# BinaryClock_Control.net
KiCad netlist of a schematic drawn in Altium Designer
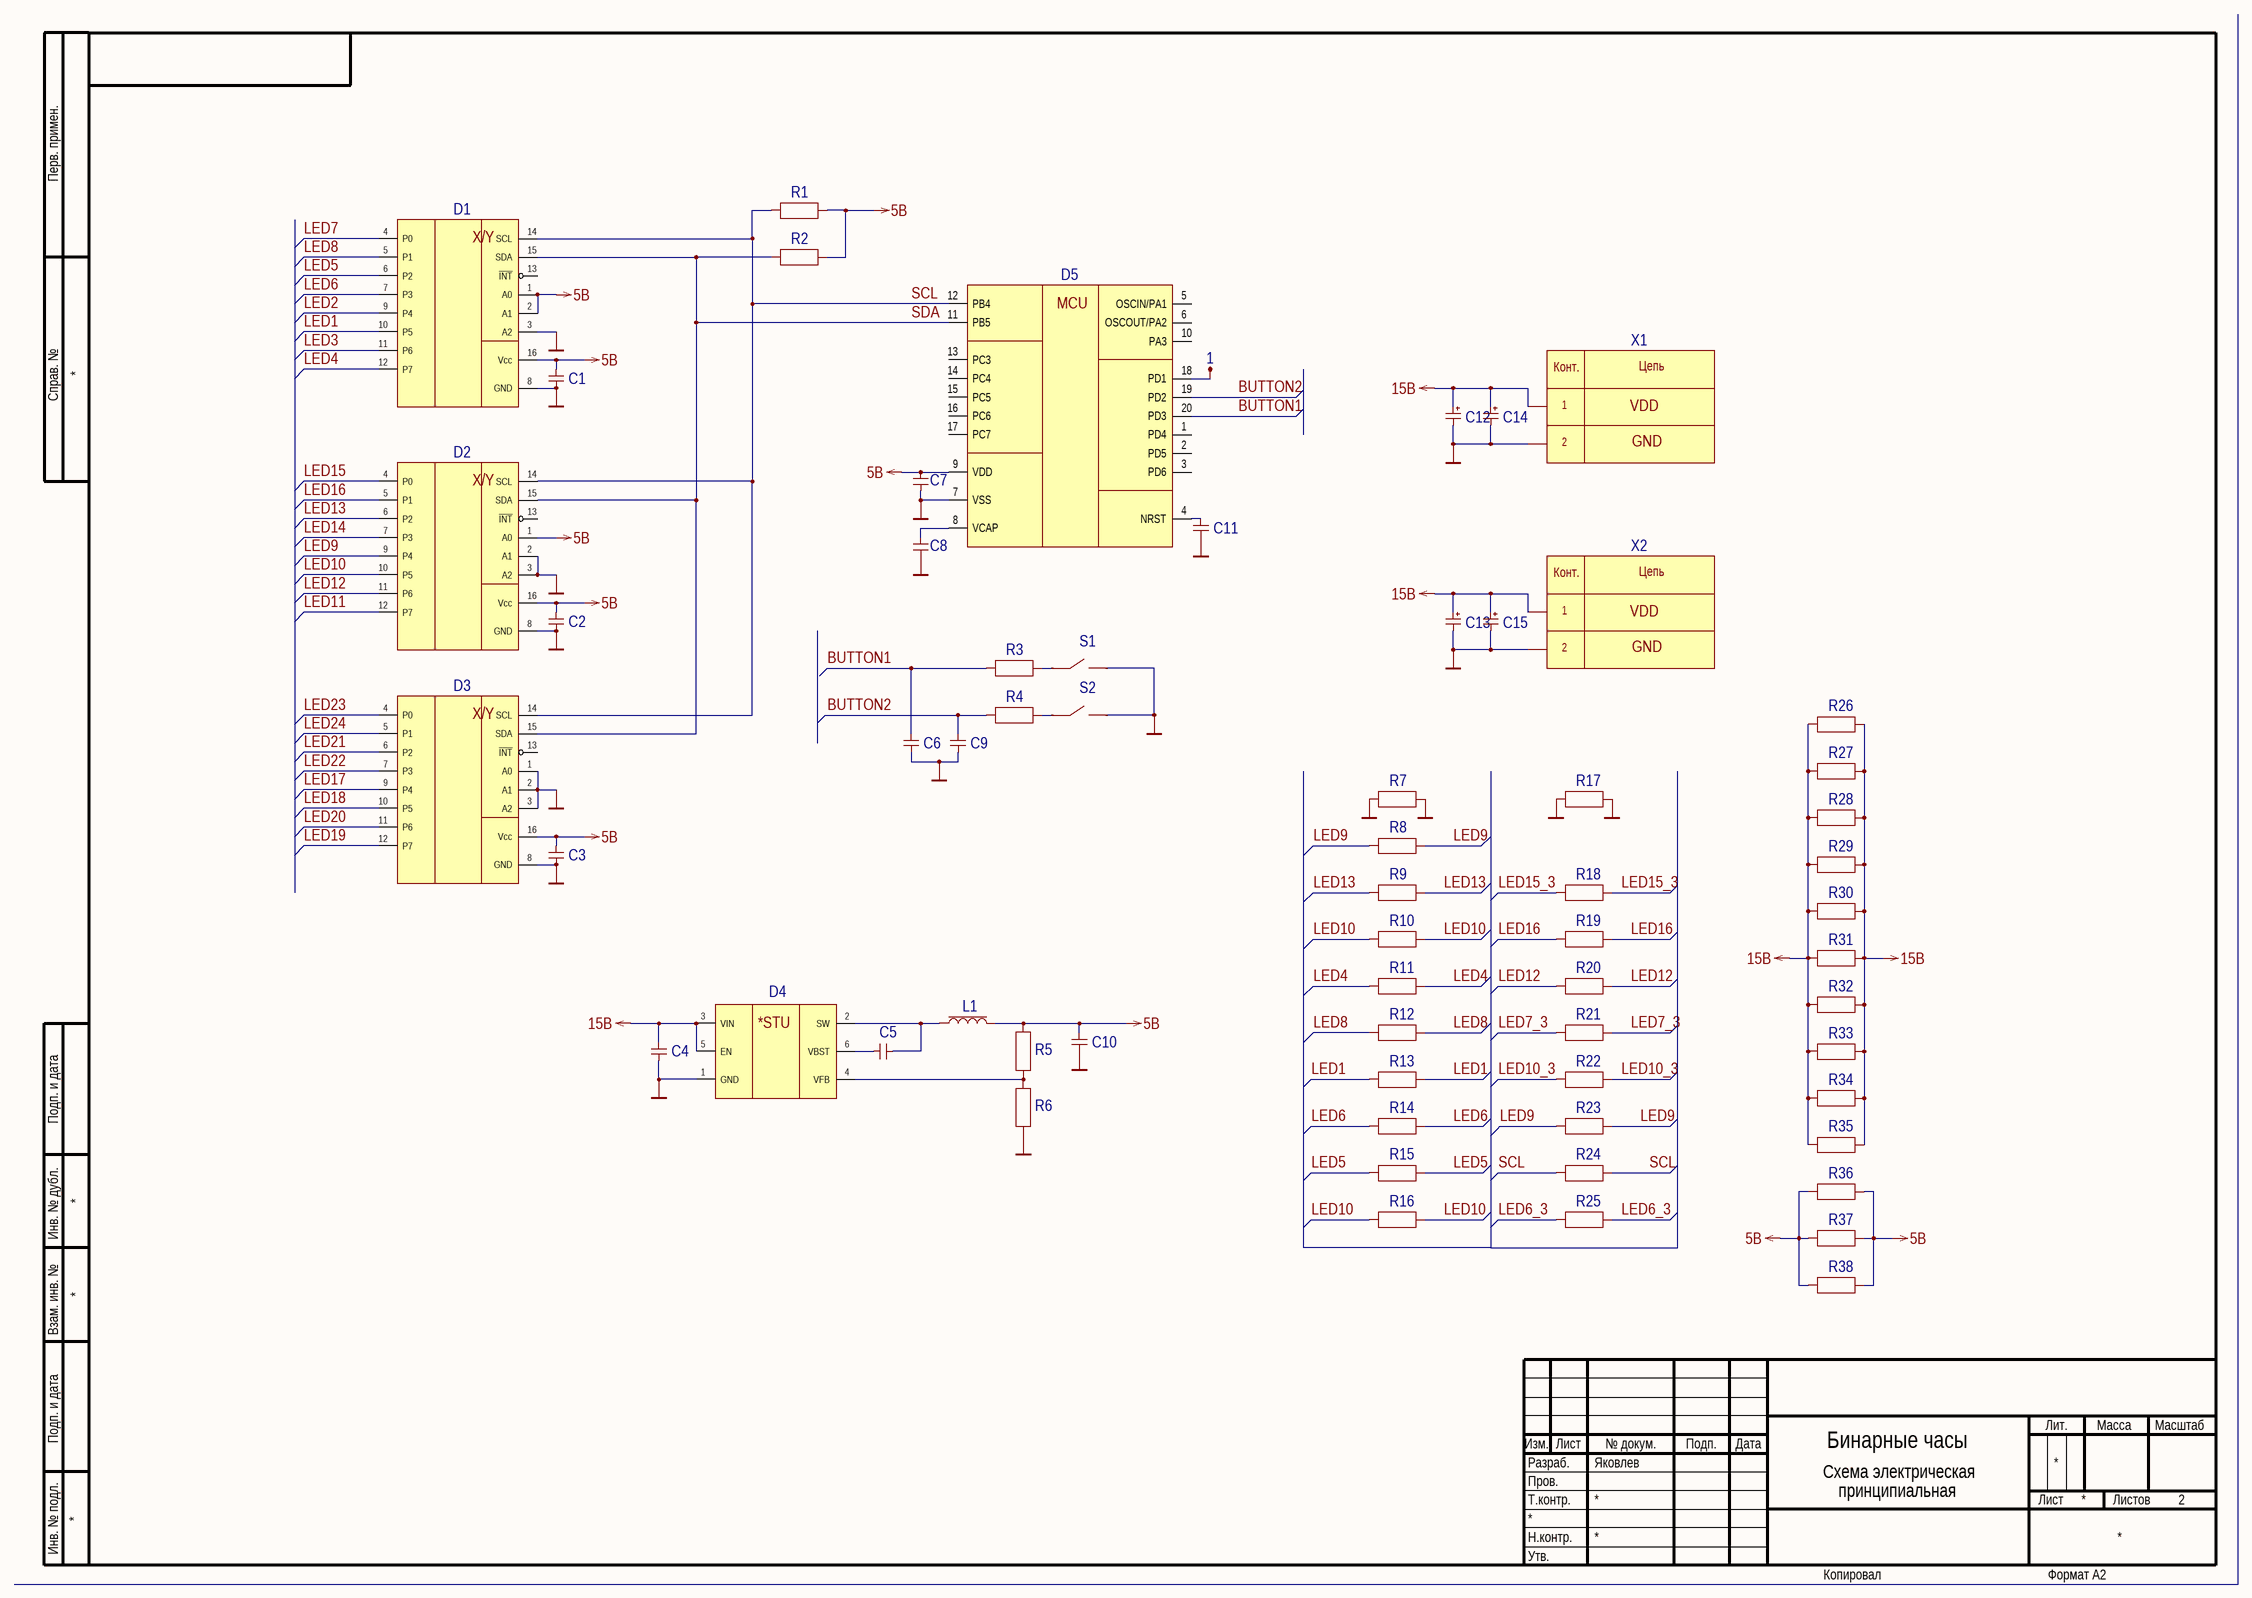
[diagram p0: BinaryClock_Control.SchDoc]

(export (version "E")
  (design (tool "Eeschema 10.0.6"))
  (components
    (comp (ref "1") (value "Point") (footprint "point") (libsource (lib "Passive,Diodes") (part "Point")))
    (comp (ref "C1")
      (value "0805-16 В-X7R-0,1мкФ±10 %")
      (footprint "SMD-0805C")
      (description "Capacitor")
      (fields (field (name "MANUFACTURER") "Murata"))
      (libsource (lib "Passive,Diodes") (part "Cap"))
    )
    (comp (ref "C2")
      (value "0805-16 В-X7R-0,1мкФ±10 %")
      (footprint "SMD-0805C")
      (description "Capacitor")
      (fields (field (name "MANUFACTURER") "Murata"))
      (libsource (lib "Passive,Diodes") (part "Cap"))
    )
    (comp (ref "C3")
      (value "0805-16 В-X7R-0,1мкФ±10 %")
      (footprint "SMD-0805C")
      (description "Capacitor")
      (fields (field (name "MANUFACTURER") "Murata"))
      (libsource (lib "Passive,Diodes") (part "Cap"))
    )
    (comp (ref "C4")
      (value "1206-16 В-X7R-22мкФ±10 %")
      (footprint "SMD-1206C")
      (description "Capacitor")
      (libsource (lib "Passive,Diodes") (part "Cap"))
    )
    (comp (ref "C5")
      (value "0805-16 В-X7R-0,1мкФ±10 %")
      (footprint "SMD-0805C")
      (description "Capacitor")
      (fields (field (name "MANUFACTURER") "Murata"))
      (libsource (lib "Passive,Diodes") (part "Cap"))
    )
    (comp (ref "C6")
      (value "0805-16 В-X7R-0,1мкФ±10 %")
      (footprint "SMD-0805C")
      (description "Capacitor")
      (fields (field (name "MANUFACTURER") "Murata"))
      (libsource (lib "Passive,Diodes") (part "Cap"))
    )
    (comp (ref "C7")
      (value "0805-16 В-X7R-0,1мкФ±10 %")
      (footprint "SMD-0805C")
      (description "Capacitor")
      (fields (field (name "MANUFACTURER") "Murata"))
      (libsource (lib "Passive,Diodes") (part "Cap"))
    )
    (comp (ref "C8")
      (value "0805-16 В-X7R-1мкФ±10 %")
      (footprint "SMD-0805C")
      (description "Capacitor")
      (fields (field (name "MANUFACTURER") "Murata"))
      (libsource (lib "Passive,Diodes") (part "Cap"))
    )
    (comp (ref "C9")
      (value "0805-16 В-X7R-0,1мкФ±10 %")
      (footprint "SMD-0805C")
      (description "Capacitor")
      (fields (field (name "MANUFACTURER") "Murata"))
      (libsource (lib "Passive,Diodes") (part "Cap"))
    )
    (comp (ref "C10")
      (value "1206-16 В-X7R-22мкФ±10 %")
      (footprint "SMD-1206C")
      (description "Capacitor")
      (libsource (lib "Passive,Diodes") (part "Cap"))
    )
    (comp (ref "C11")
      (value "0805-16 В-X7R-0,1мкФ±10 %")
      (footprint "SMD-0805C")
      (description "Capacitor")
      (fields (field (name "MANUFACTURER") "Murata"))
      (libsource (lib "Passive,Diodes") (part "Cap"))
    )
    (comp (ref "C12")
      (value "D-20 В-47 мкФ±10 %")
      (footprint "CAP POL 2917/7343")
      (description "Electrolytic capacitor")
      (libsource (lib "Passive,Diodes") (part "Cap_el"))
    )
    (comp (ref "C13")
      (value "D-20 В-47 мкФ±10 %")
      (footprint "CAP POL 2917/7343")
      (description "Electrolytic capacitor")
      (libsource (lib "Passive,Diodes") (part "Cap_el"))
    )
    (comp (ref "C14")
      (value "D-20 В-47 мкФ±10 %")
      (footprint "CAP POL 2917/7343")
      (description "Electrolytic capacitor")
      (libsource (lib "Passive,Diodes") (part "Cap_el"))
    )
    (comp (ref "C15")
      (value "D-20 В-47 мкФ±10 %")
      (footprint "CAP POL 2917/7343")
      (description "Electrolytic capacitor")
      (libsource (lib "Passive,Diodes") (part "Cap_el"))
    )
    (comp (ref "D1")
      (value "PCF8574T/3.512")
      (footprint "SO-16")
      (description "Remote 8-bit I/O expander for I2C bus")
      (fields (field (name "MANUFACTURER") "NXP"))
      (libsource (lib "Devices") (part "PCF8574"))
    )
    (comp (ref "D2")
      (value "PCF8574T/3.512")
      (footprint "SO-16")
      (description "Remote 8-bit I/O expander for I2C bus")
      (fields (field (name "MANUFACTURER") "NXP"))
      (libsource (lib "Devices") (part "PCF8574"))
    )
    (comp (ref "D3")
      (value "PCF8574T/3.512")
      (footprint "SO-16")
      (description "Remote 8-bit I/O expander for I2C bus")
      (fields (field (name "MANUFACTURER") "NXP"))
      (libsource (lib "Devices") (part "PCF8574"))
    )
    (comp (ref "D4")
      (value "TPS562200DDCT")
      (footprint "SOT23-6_M")
      (description "4.5-V To 17-V Input, 2-A, 3-A Synchronous Step-Down Voltage Regulator")
      (fields (field (name "MANUFACTURER") "Texas Instruments"))
      (libsource (lib "Devices") (part "TPS562200"))
    )
    (comp (ref "D5")
      (value "STM8S103F3P6")
      (footprint "TSSOP-20")
      (fields (field (name "MANUFACTURER") "STMicroelectronics"))
      (libsource (lib "Devices") (part "STM8S103FxP"))
    )
    (comp (ref "L1")
      (value "NLCV32T-4R7M-EF")
      (footprint "1210_M")
      (description "Inductor")
      (fields (field (name "MANUFACTURER") "TDK"))
      (libsource (lib "Passive,Diodes") (part "Inductor"))
    )
    (comp (ref "R1")
      (value "0805±5 %-10 кОм")
      (footprint "SMD-0805-RES")
      (description "Resistor")
      (libsource (lib "Passive,Diodes") (part "Res"))
    )
    (comp (ref "R2")
      (value "0805±5 %-10 кОм")
      (footprint "SMD-0805-RES")
      (description "Resistor")
      (libsource (lib "Passive,Diodes") (part "Res"))
    )
    (comp (ref "R3")
      (value "0805±5 %-100 Ом")
      (footprint "SMD-0805-RES")
      (description "Resistor")
      (libsource (lib "Passive,Diodes") (part "Res"))
    )
    (comp (ref "R4")
      (value "0805±5 %-100 Ом")
      (footprint "SMD-0805-RES")
      (description "Resistor")
      (libsource (lib "Passive,Diodes") (part "Res"))
    )
    (comp (ref "R5")
      (value "0805±1 %-56,2 кОм")
      (footprint "SMD-0805-RES")
      (description "Resistor")
      (libsource (lib "Passive,Diodes") (part "Res"))
    )
    (comp (ref "R6")
      (value "0805±1 %-10,2 кОм")
      (footprint "SMD-0805-RES")
      (description "Resistor")
      (libsource (lib "Passive,Diodes") (part "Res"))
    )
    (comp (ref "R7")
      (value "0805±5 %-0 Ом")
      (footprint "R1206")
      (description "Resistor")
      (libsource (lib "Passive,Diodes") (part "Res"))
    )
    (comp (ref "R8")
      (value "0805±5 %-0 Ом")
      (footprint "R1206")
      (description "Resistor")
      (libsource (lib "Passive,Diodes") (part "Res"))
    )
    (comp (ref "R9")
      (value "0805±5 %-0 Ом")
      (footprint "R1206")
      (description "Resistor")
      (libsource (lib "Passive,Diodes") (part "Res"))
    )
    (comp (ref "R10")
      (value "0805±5 %-0 Ом")
      (footprint "R1206")
      (description "Resistor")
      (libsource (lib "Passive,Diodes") (part "Res"))
    )
    (comp (ref "R11")
      (value "0805±5 %-0 Ом")
      (footprint "R1206")
      (description "Resistor")
      (libsource (lib "Passive,Diodes") (part "Res"))
    )
    (comp (ref "R12")
      (value "0805±5 %-0 Ом")
      (footprint "R1206")
      (description "Resistor")
      (libsource (lib "Passive,Diodes") (part "Res"))
    )
    (comp (ref "R13")
      (value "0805±5 %-0 Ом")
      (footprint "R1206")
      (description "Resistor")
      (libsource (lib "Passive,Diodes") (part "Res"))
    )
    (comp (ref "R14")
      (value "0805±5 %-0 Ом")
      (footprint "R1206")
      (description "Resistor")
      (libsource (lib "Passive,Diodes") (part "Res"))
    )
    (comp (ref "R15")
      (value "0805±5 %-0 Ом")
      (footprint "R1206")
      (description "Resistor")
      (libsource (lib "Passive,Diodes") (part "Res"))
    )
    (comp (ref "R16")
      (value "0805±5 %-0 Ом")
      (footprint "R1206")
      (description "Resistor")
      (libsource (lib "Passive,Diodes") (part "Res"))
    )
    (comp (ref "R17")
      (value "0805±5 %-0 Ом")
      (footprint "R1206")
      (description "Resistor")
      (libsource (lib "Passive,Diodes") (part "Res"))
    )
    (comp (ref "R18")
      (value "0805±5 %-0 Ом")
      (footprint "R1206")
      (description "Resistor")
      (libsource (lib "Passive,Diodes") (part "Res"))
    )
    (comp (ref "R19")
      (value "0805±5 %-0 Ом")
      (footprint "R1206")
      (description "Resistor")
      (libsource (lib "Passive,Diodes") (part "Res"))
    )
    (comp (ref "R20")
      (value "0805±5 %-0 Ом")
      (footprint "R1206")
      (description "Resistor")
      (libsource (lib "Passive,Diodes") (part "Res"))
    )
    (comp (ref "R21")
      (value "0805±5 %-0 Ом")
      (footprint "R1206")
      (description "Resistor")
      (libsource (lib "Passive,Diodes") (part "Res"))
    )
    (comp (ref "R22")
      (value "0805±5 %-0 Ом")
      (footprint "R1206")
      (description "Resistor")
      (libsource (lib "Passive,Diodes") (part "Res"))
    )
    (comp (ref "R23")
      (value "0805±5 %-0 Ом")
      (footprint "R1206")
      (description "Resistor")
      (libsource (lib "Passive,Diodes") (part "Res"))
    )
    (comp (ref "R24")
      (value "0805±5 %-0 Ом")
      (footprint "R1206")
      (description "Resistor")
      (libsource (lib "Passive,Diodes") (part "Res"))
    )
    (comp (ref "R25")
      (value "0805±5 %-0 Ом")
      (footprint "R1206")
      (description "Resistor")
      (libsource (lib "Passive,Diodes") (part "Res"))
    )
    (comp (ref "R26")
      (value "0805±5 %-0 Ом")
      (footprint "R1206")
      (description "Resistor")
      (libsource (lib "Passive,Diodes") (part "Res"))
    )
    (comp (ref "R27")
      (value "0805±5 %-0 Ом")
      (footprint "R1206")
      (description "Resistor")
      (libsource (lib "Passive,Diodes") (part "Res"))
    )
    (comp (ref "R28")
      (value "0805±5 %-0 Ом")
      (footprint "R1206")
      (description "Resistor")
      (libsource (lib "Passive,Diodes") (part "Res"))
    )
    (comp (ref "R29")
      (value "0805±5 %-0 Ом")
      (footprint "R1206")
      (description "Resistor")
      (libsource (lib "Passive,Diodes") (part "Res"))
    )
    (comp (ref "R30")
      (value "0805±5 %-0 Ом")
      (footprint "R1206")
      (description "Resistor")
      (libsource (lib "Passive,Diodes") (part "Res"))
    )
    (comp (ref "R31")
      (value "0805±5 %-0 Ом")
      (footprint "R1206")
      (description "Resistor")
      (libsource (lib "Passive,Diodes") (part "Res"))
    )
    (comp (ref "R32")
      (value "0805±5 %-0 Ом")
      (footprint "R1206")
      (description "Resistor")
      (libsource (lib "Passive,Diodes") (part "Res"))
    )
    (comp (ref "R33")
      (value "0805±5 %-0 Ом")
      (footprint "R1206")
      (description "Resistor")
      (libsource (lib "Passive,Diodes") (part "Res"))
    )
    (comp (ref "R34")
      (value "0805±5 %-0 Ом")
      (footprint "R1206")
      (description "Resistor")
      (libsource (lib "Passive,Diodes") (part "Res"))
    )
    (comp (ref "R35")
      (value "0805±5 %-0 Ом")
      (footprint "R1206")
      (description "Resistor")
      (libsource (lib "Passive,Diodes") (part "Res"))
    )
    (comp (ref "R36")
      (value "0805±5 %-0 Ом")
      (footprint "R1206")
      (description "Resistor")
      (libsource (lib "Passive,Diodes") (part "Res"))
    )
    (comp (ref "R37")
      (value "0805±5 %-0 Ом")
      (footprint "R1206")
      (description "Resistor")
      (libsource (lib "Passive,Diodes") (part "Res"))
    )
    (comp (ref "R38")
      (value "0805±5 %-0 Ом")
      (footprint "R1206")
      (description "Resistor")
      (libsource (lib "Passive,Diodes") (part "Res"))
    )
    (comp (ref "S1")
      (value "1243SHIM-160G-G")
      (footprint "1243S")
      (description "Tact button SPST")
      (fields (field (name "MANUFACTURER") "Switronic"))
      (libsource (lib "Connectors") (part "button"))
    )
    (comp (ref "S2")
      (value "1243SHIM-160G-G")
      (footprint "1243S")
      (description "Tact button SPST")
      (fields (field (name "MANUFACTURER") "Switronic"))
      (libsource (lib "Connectors") (part "button"))
    )
    (comp (ref "X1")
      (value "RASM712X")
      (footprint "RASM712")
      (description "Power jack 2.5 mm SMD connector")
      (fields (field (name "MANUFACTURER") "Switchcraft"))
      (libsource (lib "Connectors") (part "RASM712X"))
    )
    (comp (ref "X2")
      (value "RASM712X")
      (footprint "RASM712")
      (description "Power jack 2.5 mm SMD connector")
      (fields (field (name "MANUFACTURER") "Switchcraft"))
      (libsource (lib "Connectors") (part "RASM712X"))
    )
  )
  (nets
    (net (code "1") (name "/BUTTON1") (class "Default")
      (node (ref "C6") (pin "2") (pinfunction "2_2") (pintype "passive"))
      (node (ref "D5") (pin "20") (pinfunction "PD3_20") (pintype "passive"))
      (node (ref "R3") (pin "1") (pinfunction "1_1") (pintype "passive"))
    )
    (net (code "2") (name "/BUTTON2") (class "Default")
      (node (ref "C9") (pin "2") (pinfunction "2_2") (pintype "passive"))
      (node (ref "D5") (pin "19") (pinfunction "PD2_19") (pintype "passive"))
      (node (ref "R4") (pin "1") (pinfunction "1_1") (pintype "passive"))
    )
    (net (code "3") (name "/LED1") (class "Default")
      (node (ref "D1") (pin "10") (pinfunction "P5_10") (pintype "passive"))
      (node (ref "R13") (pin "1") (pinfunction "1_1") (pintype "passive"))
      (node (ref "R13") (pin "2") (pinfunction "2_2") (pintype "passive"))
    )
    (net (code "4") (name "/LED2") (class "Default")
      (node (ref "D1") (pin "9") (pinfunction "P4_9") (pintype "passive"))
    )
    (net (code "5") (name "/LED3") (class "Default")
      (node (ref "D1") (pin "11") (pinfunction "P6_11") (pintype "passive"))
    )
    (net (code "6") (name "/LED4") (class "Default")
      (node (ref "D1") (pin "12") (pinfunction "P7_12") (pintype "passive"))
      (node (ref "R11") (pin "1") (pinfunction "1_1") (pintype "passive"))
      (node (ref "R11") (pin "2") (pinfunction "2_2") (pintype "passive"))
    )
    (net (code "7") (name "/LED5") (class "Default")
      (node (ref "D1") (pin "6") (pinfunction "P2_6") (pintype "passive"))
      (node (ref "R15") (pin "1") (pinfunction "1_1") (pintype "passive"))
      (node (ref "R15") (pin "2") (pinfunction "2_2") (pintype "passive"))
    )
    (net (code "8") (name "/LED6") (class "Default")
      (node (ref "D1") (pin "7") (pinfunction "P3_7") (pintype "passive"))
      (node (ref "R14") (pin "1") (pinfunction "1_1") (pintype "passive"))
      (node (ref "R14") (pin "2") (pinfunction "2_2") (pintype "passive"))
    )
    (net (code "9") (name "/LED6_3") (class "Default")
      (node (ref "R25") (pin "1") (pinfunction "1_1") (pintype "passive"))
      (node (ref "R25") (pin "2") (pinfunction "2_2") (pintype "passive"))
    )
    (net (code "10") (name "/LED7") (class "Default")
      (node (ref "D1") (pin "4") (pinfunction "P0_4") (pintype "passive"))
    )
    (net (code "11") (name "/LED7_3") (class "Default")
      (node (ref "R21") (pin "1") (pinfunction "1_1") (pintype "passive"))
      (node (ref "R21") (pin "2") (pinfunction "2_2") (pintype "passive"))
    )
    (net (code "12") (name "/LED8") (class "Default")
      (node (ref "D1") (pin "5") (pinfunction "P1_5") (pintype "passive"))
      (node (ref "R12") (pin "1") (pinfunction "1_1") (pintype "passive"))
      (node (ref "R12") (pin "2") (pinfunction "2_2") (pintype "passive"))
    )
    (net (code "13") (name "/LED9") (class "Default")
      (node (ref "D2") (pin "9") (pinfunction "P4_9") (pintype "passive"))
      (node (ref "R23") (pin "1") (pinfunction "1_1") (pintype "passive"))
      (node (ref "R23") (pin "2") (pinfunction "2_2") (pintype "passive"))
      (node (ref "R8") (pin "1") (pinfunction "1_1") (pintype "passive"))
      (node (ref "R8") (pin "2") (pinfunction "2_2") (pintype "passive"))
    )
    (net (code "14") (name "/LED10") (class "Default")
      (node (ref "D2") (pin "10") (pinfunction "P5_10") (pintype "passive"))
      (node (ref "R10") (pin "1") (pinfunction "1_1") (pintype "passive"))
      (node (ref "R10") (pin "2") (pinfunction "2_2") (pintype "passive"))
      (node (ref "R16") (pin "1") (pinfunction "1_1") (pintype "passive"))
      (node (ref "R16") (pin "2") (pinfunction "2_2") (pintype "passive"))
    )
    (net (code "15") (name "/LED10_3") (class "Default")
      (node (ref "R22") (pin "1") (pinfunction "1_1") (pintype "passive"))
      (node (ref "R22") (pin "2") (pinfunction "2_2") (pintype "passive"))
    )
    (net (code "16") (name "/LED11") (class "Default")
      (node (ref "D2") (pin "12") (pinfunction "P7_12") (pintype "passive"))
    )
    (net (code "17") (name "/LED12") (class "Default")
      (node (ref "D2") (pin "11") (pinfunction "P6_11") (pintype "passive"))
      (node (ref "R20") (pin "1") (pinfunction "1_1") (pintype "passive"))
      (node (ref "R20") (pin "2") (pinfunction "2_2") (pintype "passive"))
    )
    (net (code "18") (name "/LED13") (class "Default")
      (node (ref "D2") (pin "6") (pinfunction "P2_6") (pintype "passive"))
      (node (ref "R9") (pin "1") (pinfunction "1_1") (pintype "passive"))
      (node (ref "R9") (pin "2") (pinfunction "2_2") (pintype "passive"))
    )
    (net (code "19") (name "/LED14") (class "Default")
      (node (ref "D2") (pin "7") (pinfunction "P3_7") (pintype "passive"))
    )
    (net (code "20") (name "/LED15") (class "Default")
      (node (ref "D2") (pin "4") (pinfunction "P0_4") (pintype "passive"))
    )
    (net (code "21") (name "/LED15_3") (class "Default")
      (node (ref "R18") (pin "1") (pinfunction "1_1") (pintype "passive"))
      (node (ref "R18") (pin "2") (pinfunction "2_2") (pintype "passive"))
    )
    (net (code "22") (name "/LED16") (class "Default")
      (node (ref "D2") (pin "5") (pinfunction "P1_5") (pintype "passive"))
      (node (ref "R19") (pin "1") (pinfunction "1_1") (pintype "passive"))
      (node (ref "R19") (pin "2") (pinfunction "2_2") (pintype "passive"))
    )
    (net (code "23") (name "/LED17") (class "Default")
      (node (ref "D3") (pin "9") (pinfunction "P4_9") (pintype "passive"))
    )
    (net (code "24") (name "/LED18") (class "Default")
      (node (ref "D3") (pin "10") (pinfunction "P5_10") (pintype "passive"))
    )
    (net (code "25") (name "/LED19") (class "Default")
      (node (ref "D3") (pin "12") (pinfunction "P7_12") (pintype "passive"))
    )
    (net (code "26") (name "/LED20") (class "Default")
      (node (ref "D3") (pin "11") (pinfunction "P6_11") (pintype "passive"))
    )
    (net (code "27") (name "/LED21") (class "Default")
      (node (ref "D3") (pin "6") (pinfunction "P2_6") (pintype "passive"))
    )
    (net (code "28") (name "/LED22") (class "Default")
      (node (ref "D3") (pin "7") (pinfunction "P3_7") (pintype "passive"))
    )
    (net (code "29") (name "/LED23") (class "Default")
      (node (ref "D3") (pin "4") (pinfunction "P0_4") (pintype "passive"))
    )
    (net (code "30") (name "/LED24") (class "Default")
      (node (ref "D3") (pin "5") (pinfunction "P1_5") (pintype "passive"))
    )
    (net (code "31") (name "/SCL") (class "Default")
      (node (ref "D1") (pin "14") (pinfunction "SCL_14") (pintype "passive"))
      (node (ref "D2") (pin "14") (pinfunction "SCL_14") (pintype "passive"))
      (node (ref "D3") (pin "14") (pinfunction "SCL_14") (pintype "passive"))
      (node (ref "D5") (pin "12") (pinfunction "PB4_12") (pintype "passive"))
      (node (ref "R1") (pin "1") (pinfunction "1_1") (pintype "passive"))
      (node (ref "R24") (pin "1") (pinfunction "1_1") (pintype "passive"))
      (node (ref "R24") (pin "2") (pinfunction "2_2") (pintype "passive"))
    )
    (net (code "32") (name "/SDA") (class "Default")
      (node (ref "D1") (pin "15") (pinfunction "SDA_15") (pintype "passive"))
      (node (ref "D2") (pin "15") (pinfunction "SDA_15") (pintype "passive"))
      (node (ref "D3") (pin "15") (pinfunction "SDA_15") (pintype "passive"))
      (node (ref "D5") (pin "11") (pinfunction "PB5_11") (pintype "passive"))
      (node (ref "R2") (pin "1") (pinfunction "1_1") (pintype "passive"))
    )
    (net (code "33") (name "5В") (class "Default")
      (node (ref "C1") (pin "2") (pinfunction "2_2") (pintype "passive"))
      (node (ref "C10") (pin "2") (pinfunction "2_2") (pintype "passive"))
      (node (ref "C2") (pin "2") (pinfunction "2_2") (pintype "passive"))
      (node (ref "C3") (pin "2") (pinfunction "2_2") (pintype "passive"))
      (node (ref "C7") (pin "2") (pinfunction "2_2") (pintype "passive"))
      (node (ref "D1") (pin "1") (pinfunction "A0_1") (pintype "passive"))
      (node (ref "D1") (pin "16") (pinfunction "Vcc_16") (pintype "power_in"))
      (node (ref "D1") (pin "2") (pinfunction "A1_2") (pintype "passive"))
      (node (ref "D2") (pin "1") (pinfunction "A0_1") (pintype "passive"))
      (node (ref "D2") (pin "16") (pinfunction "Vcc_16") (pintype "power_in"))
      (node (ref "D3") (pin "16") (pinfunction "Vcc_16") (pintype "power_in"))
      (node (ref "D5") (pin "9") (pinfunction "VDD_9") (pintype "power_in"))
      (node (ref "L1") (pin "2") (pinfunction "2_2") (pintype "passive"))
      (node (ref "R1") (pin "2") (pinfunction "2_2") (pintype "passive"))
      (node (ref "R2") (pin "2") (pinfunction "2_2") (pintype "passive"))
      (node (ref "R36") (pin "1") (pinfunction "1_1") (pintype "passive"))
      (node (ref "R36") (pin "2") (pinfunction "2_2") (pintype "passive"))
      (node (ref "R37") (pin "1") (pinfunction "1_1") (pintype "passive"))
      (node (ref "R37") (pin "2") (pinfunction "2_2") (pintype "passive"))
      (node (ref "R38") (pin "1") (pinfunction "1_1") (pintype "passive"))
      (node (ref "R38") (pin "2") (pinfunction "2_2") (pintype "passive"))
      (node (ref "R5") (pin "2") (pinfunction "2_2") (pintype "passive"))
    )
    (net (code "34") (name "15В") (class "Default")
      (node (ref "C12") (pin "1") (pinfunction "1_1") (pintype "passive"))
      (node (ref "C13") (pin "1") (pinfunction "1_1") (pintype "passive"))
      (node (ref "C14") (pin "1") (pinfunction "1_1") (pintype "passive"))
      (node (ref "C15") (pin "1") (pinfunction "1_1") (pintype "passive"))
      (node (ref "C4") (pin "2") (pinfunction "2_2") (pintype "passive"))
      (node (ref "D4") (pin "3") (pinfunction "VIN_3") (pintype "power_in"))
      (node (ref "D4") (pin "5") (pinfunction "EN_5") (pintype "passive"))
      (node (ref "R26") (pin "1") (pinfunction "1_1") (pintype "passive"))
      (node (ref "R26") (pin "2") (pinfunction "2_2") (pintype "passive"))
      (node (ref "R27") (pin "1") (pinfunction "1_1") (pintype "passive"))
      (node (ref "R27") (pin "2") (pinfunction "2_2") (pintype "passive"))
      (node (ref "R28") (pin "1") (pinfunction "1_1") (pintype "passive"))
      (node (ref "R28") (pin "2") (pinfunction "2_2") (pintype "passive"))
      (node (ref "R29") (pin "1") (pinfunction "1_1") (pintype "passive"))
      (node (ref "R29") (pin "2") (pinfunction "2_2") (pintype "passive"))
      (node (ref "R30") (pin "1") (pinfunction "1_1") (pintype "passive"))
      (node (ref "R30") (pin "2") (pinfunction "2_2") (pintype "passive"))
      (node (ref "R31") (pin "1") (pinfunction "1_1") (pintype "passive"))
      (node (ref "R31") (pin "2") (pinfunction "2_2") (pintype "passive"))
      (node (ref "R32") (pin "1") (pinfunction "1_1") (pintype "passive"))
      (node (ref "R32") (pin "2") (pinfunction "2_2") (pintype "passive"))
      (node (ref "R33") (pin "1") (pinfunction "1_1") (pintype "passive"))
      (node (ref "R33") (pin "2") (pinfunction "2_2") (pintype "passive"))
      (node (ref "R34") (pin "1") (pinfunction "1_1") (pintype "passive"))
      (node (ref "R34") (pin "2") (pinfunction "2_2") (pintype "passive"))
      (node (ref "R35") (pin "1") (pinfunction "1_1") (pintype "passive"))
      (node (ref "R35") (pin "2") (pinfunction "2_2") (pintype "passive"))
      (node (ref "X1") (pin "1") (pinfunction "1_1") (pintype "passive"))
      (node (ref "X2") (pin "1") (pinfunction "1_1") (pintype "passive"))
    )
    (net (code "35") (name "GND") (class "Default")
      (node (ref "C1") (pin "1") (pinfunction "1_1") (pintype "passive"))
      (node (ref "C10") (pin "1") (pinfunction "1_1") (pintype "passive"))
      (node (ref "C11") (pin "1") (pinfunction "1_1") (pintype "passive"))
      (node (ref "C12") (pin "2") (pinfunction "2_2") (pintype "passive"))
      (node (ref "C13") (pin "2") (pinfunction "2_2") (pintype "passive"))
      (node (ref "C14") (pin "2") (pinfunction "2_2") (pintype "passive"))
      (node (ref "C15") (pin "2") (pinfunction "2_2") (pintype "passive"))
      (node (ref "C2") (pin "1") (pinfunction "1_1") (pintype "passive"))
      (node (ref "C3") (pin "1") (pinfunction "1_1") (pintype "passive"))
      (node (ref "C4") (pin "1") (pinfunction "1_1") (pintype "passive"))
      (node (ref "C6") (pin "1") (pinfunction "1_1") (pintype "passive"))
      (node (ref "C7") (pin "1") (pinfunction "1_1") (pintype "passive"))
      (node (ref "C8") (pin "1") (pinfunction "1_1") (pintype "passive"))
      (node (ref "C9") (pin "1") (pinfunction "1_1") (pintype "passive"))
      (node (ref "D1") (pin "3") (pinfunction "A2_3") (pintype "passive"))
      (node (ref "D1") (pin "8") (pinfunction "GND_8") (pintype "power_in"))
      (node (ref "D2") (pin "2") (pinfunction "A1_2") (pintype "passive"))
      (node (ref "D2") (pin "3") (pinfunction "A2_3") (pintype "passive"))
      (node (ref "D2") (pin "8") (pinfunction "GND_8") (pintype "power_in"))
      (node (ref "D3") (pin "1") (pinfunction "A0_1") (pintype "passive"))
      (node (ref "D3") (pin "2") (pinfunction "A1_2") (pintype "passive"))
      (node (ref "D3") (pin "3") (pinfunction "A2_3") (pintype "passive"))
      (node (ref "D3") (pin "8") (pinfunction "GND_8") (pintype "power_in"))
      (node (ref "D4") (pin "1") (pinfunction "GND_1") (pintype "power_in"))
      (node (ref "D5") (pin "7") (pinfunction "VSS_7") (pintype "power_in"))
      (node (ref "R17") (pin "1") (pinfunction "1_1") (pintype "passive"))
      (node (ref "R17") (pin "2") (pinfunction "2_2") (pintype "passive"))
      (node (ref "R6") (pin "1") (pinfunction "1_1") (pintype "passive"))
      (node (ref "R7") (pin "1") (pinfunction "1_1") (pintype "passive"))
      (node (ref "R7") (pin "2") (pinfunction "2_2") (pintype "passive"))
      (node (ref "S1") (pin "2") (pinfunction "2_2") (pintype "passive"))
      (node (ref "S2") (pin "2") (pinfunction "2_2") (pintype "passive"))
      (node (ref "X1") (pin "2") (pinfunction "2_2") (pintype "passive"))
      (node (ref "X2") (pin "2") (pinfunction "2_2") (pintype "passive"))
    )
    (net (code "36") (name "Net-(D4-SW)") (class "Default")
      (node (ref "C5") (pin "1") (pinfunction "1_1") (pintype "passive"))
      (node (ref "D4") (pin "2") (pinfunction "SW_2") (pintype "passive"))
      (node (ref "L1") (pin "1") (pinfunction "1_1") (pintype "passive"))
    )
    (net (code "37") (name "Net-(D4-VBST)") (class "Default")
      (node (ref "C5") (pin "2") (pinfunction "2_2") (pintype "passive"))
      (node (ref "D4") (pin "6") (pinfunction "VBST_6") (pintype "passive"))
    )
    (net (code "38") (name "Net-(D4-VFB)") (class "Default")
      (node (ref "D4") (pin "4") (pinfunction "VFB_4") (pintype "passive"))
      (node (ref "R5") (pin "1") (pinfunction "1_1") (pintype "passive"))
      (node (ref "R6") (pin "2") (pinfunction "2_2") (pintype "passive"))
    )
    (net (code "39") (name "Net-(D5-NRST)") (class "Default")
      (node (ref "C11") (pin "2") (pinfunction "2_2") (pintype "passive"))
      (node (ref "D5") (pin "4") (pinfunction "NRST_4") (pintype "passive"))
    )
    (net (code "40") (name "Net-(D5-PD1)") (class "Default")
      (node (ref "1") (pin "1") (pintype "passive"))
      (node (ref "D5") (pin "18") (pinfunction "PD1_18") (pintype "passive"))
    )
    (net (code "41") (name "Net-(D5-VCAP)") (class "Default")
      (node (ref "C8") (pin "2") (pinfunction "2_2") (pintype "passive"))
      (node (ref "D5") (pin "8") (pinfunction "VCAP_8") (pintype "passive"))
    )
    (net (code "42") (name "Net-(R3-Pad2)") (class "Default")
      (node (ref "R3") (pin "2") (pinfunction "2_2") (pintype "passive"))
      (node (ref "S1") (pin "1") (pinfunction "1_1") (pintype "passive"))
    )
    (net (code "43") (name "Net-(R4-Pad2)") (class "Default")
      (node (ref "R4") (pin "2") (pinfunction "2_2") (pintype "passive"))
      (node (ref "S2") (pin "1") (pinfunction "1_1") (pintype "passive"))
    )
    (net (code "44") (name "unconnected-(D1-~{INT}-Pad13)") (class "Default")
      (node (ref "D1") (pin "13") (pinfunction "~{INT}_13") (pintype "passive"))
    )
    (net (code "45") (name "unconnected-(D2-~{INT}-Pad13)") (class "Default")
      (node (ref "D2") (pin "13") (pinfunction "~{INT}_13") (pintype "passive"))
    )
    (net (code "46") (name "unconnected-(D3-~{INT}-Pad13)") (class "Default")
      (node (ref "D3") (pin "13") (pinfunction "~{INT}_13") (pintype "passive"))
    )
    (net (code "47") (name "unconnected-(D5-OSCIN{slash}PA1-Pad5)") (class "Default")
      (node (ref "D5") (pin "5") (pinfunction "OSCIN/PA1_5") (pintype "passive"))
    )
    (net (code "48") (name "unconnected-(D5-OSCOUT{slash}PA2-Pad6)") (class "Default")
      (node (ref "D5") (pin "6") (pinfunction "OSCOUT/PA2_6") (pintype "passive"))
    )
    (net (code "49") (name "unconnected-(D5-PA3-Pad10)") (class "Default")
      (node (ref "D5") (pin "10") (pinfunction "PA3_10") (pintype "passive"))
    )
    (net (code "50") (name "unconnected-(D5-PC3-Pad13)") (class "Default")
      (node (ref "D5") (pin "13") (pinfunction "PC3_13") (pintype "passive"))
    )
    (net (code "51") (name "unconnected-(D5-PC4-Pad14)") (class "Default")
      (node (ref "D5") (pin "14") (pinfunction "PC4_14") (pintype "passive"))
    )
    (net (code "52") (name "unconnected-(D5-PC5-Pad15)") (class "Default")
      (node (ref "D5") (pin "15") (pinfunction "PC5_15") (pintype "passive"))
    )
    (net (code "53") (name "unconnected-(D5-PC6-Pad16)") (class "Default")
      (node (ref "D5") (pin "16") (pinfunction "PC6_16") (pintype "passive"))
    )
    (net (code "54") (name "unconnected-(D5-PC7-Pad17)") (class "Default")
      (node (ref "D5") (pin "17") (pinfunction "PC7_17") (pintype "passive"))
    )
    (net (code "55") (name "unconnected-(D5-PD4-Pad1)") (class "Default")
      (node (ref "D5") (pin "1") (pinfunction "PD4_1") (pintype "passive"))
    )
    (net (code "56") (name "unconnected-(D5-PD5-Pad2)") (class "Default")
      (node (ref "D5") (pin "2") (pinfunction "PD5_2") (pintype "passive"))
    )
    (net (code "57") (name "unconnected-(D5-PD6-Pad3)") (class "Default")
      (node (ref "D5") (pin "3") (pinfunction "PD6_3") (pintype "passive"))
    )
  )
)
